# ATMega328P-PU.net
KiCad netlist of a schematic drawn in Altium Designer
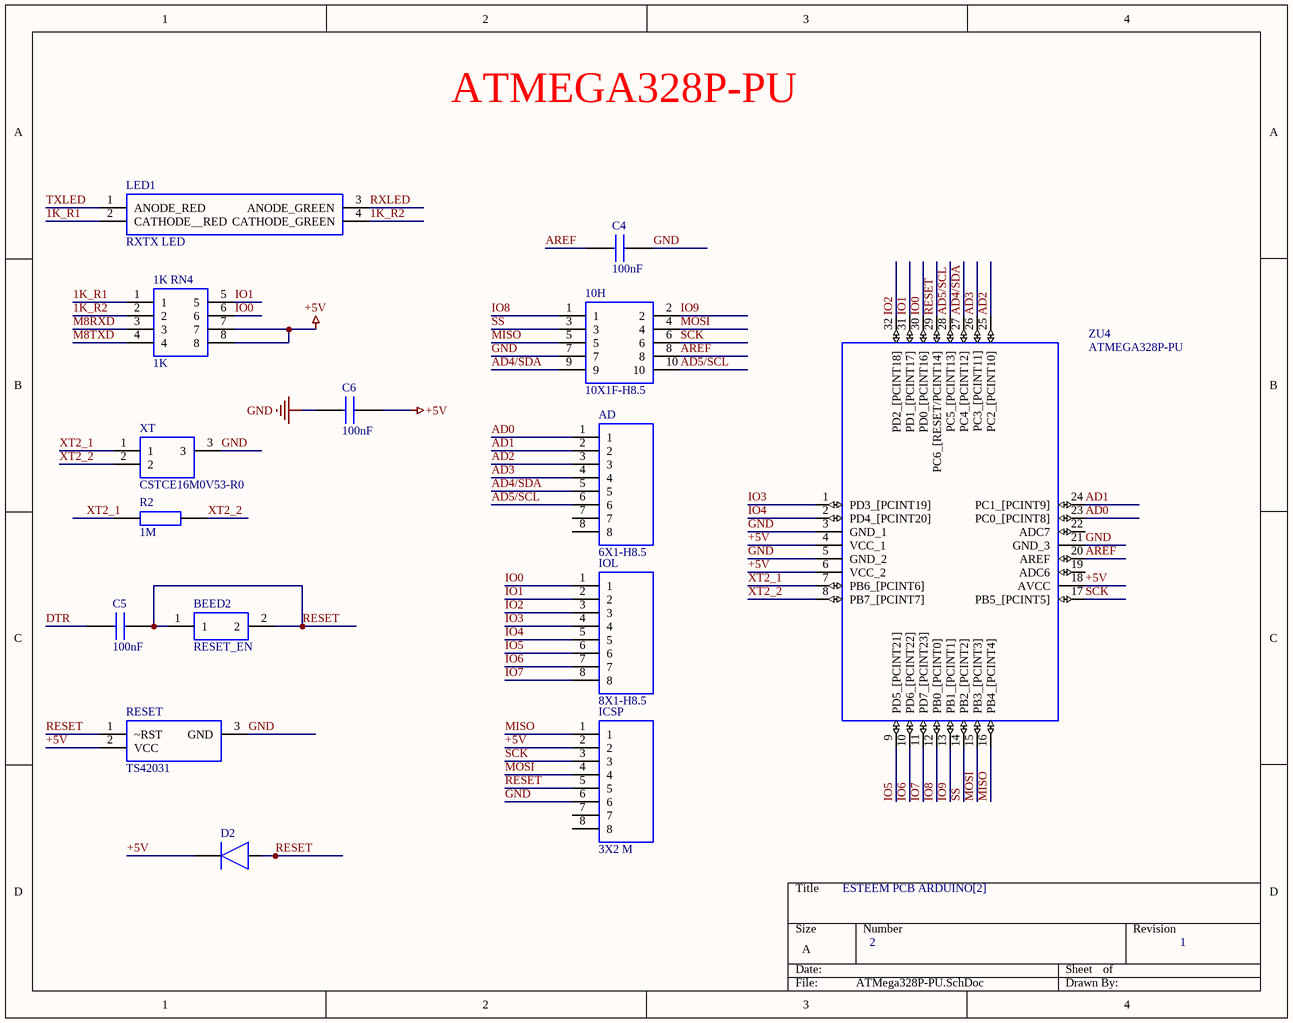
[diagram p0: ATMega328P-PU.SchDoc]

(export (version "E")
  (design (tool "Eeschema 10.0.6"))
  (components
    (comp (ref "1K RN4")
      (value "1K")
      (footprint "CAY10-XXXJ4")
      (fields
        (field (name "MANUFACTURER_PART_NUMBER") "CAY10-220J4LF")
        (field (name "RS PART NUMBER") "1674746")
        (field (name "MOUSER PART NUMBER") "652-CAY10-220J4LF")
      )
      (libsource (lib "22R RN3D") (part "CAY10-220J4LF"))
    )
    (comp (ref "10H")
      (value "10X1F-H8.5")
      (footprint "FTMH10503LDV")
      (fields
        (field (name "MANUFACTURER_PART_NUMBER") "FTMH-105-03-L-DV")
        (field (name "RS PART NUMBER") "7668984P")
        (field (name "MOUSER PART NUMBER") "200-FTMH10503LDV")
      )
      (libsource (lib "10X1F-H8.5") (part "FTMH-105-03-L-DV"))
    )
    (comp (ref "AD")
      (value "6X1-H8.5")
      (footprint "HDRV8W90P0X254_1X8_2032X249X560P")
      (fields
        (field (name "MANUFACTURER_PART_NUMBER") "90120-0768")
        (field (name "RS PART NUMBER") "1671900")
        (field (name "MOUSER PART NUMBER") "538-90120-0768")
      )
      (libsource (lib "8X1F-H8.5") (part "90120-0768"))
    )
    (comp (ref "BEED2")
      (value "RESET_EN")
      (footprint "BEADC2012X105N")
      (description "Chip Ferrite Bead 600R 0805 300mA 1LN")
      (fields
        (field (name "MANUFACTURER_PART_NUMBER") "BLM21BD601SH1D")
        (field (name "RS PART NUMBER") "1048541P")
      )
      (libsource (lib "Ferride Bead") (part "BLM21BD601SH1D"))
    )
    (comp (ref "C4")
      (value "100nF")
      (footprint "CAPC2012X130N")
      (fields
        (field (name "MANUFACTURER_PART_NUMBER") "0805Y0500104KXT")
        (field (name "RS PART NUMBER") "7738389P")
      )
      (libsource (lib "100nF") (part "0805Y0500104KXT"))
    )
    (comp (ref "C5")
      (value "100nF")
      (footprint "CAPC2012X130N")
      (fields
        (field (name "MANUFACTURER_PART_NUMBER") "0805Y0500104KXT")
        (field (name "RS PART NUMBER") "7738389P")
      )
      (libsource (lib "100nF") (part "0805Y0500104KXT"))
    )
    (comp (ref "C6")
      (value "100nF")
      (footprint "CAPC2012X130N")
      (fields
        (field (name "MANUFACTURER_PART_NUMBER") "0805Y0500104KXT")
        (field (name "RS PART NUMBER") "7738389P")
      )
      (libsource (lib "100nF") (part "0805Y0500104KXT"))
    )
    (comp (ref "D2")
      (value "CD1206-S01575")
      (footprint "DIOC3016X65N")
      (fields
        (field (name "RS PART NUMBER") "1775431")
        (field (name "MOUSER PART NUMBER") "652-CD1206-S01575")
      )
      (libsource (lib "CD1206-S01575") (part "CD1206-S01575"))
    )
    (comp (ref "ICSP")
      (value "3X2 M")
      (footprint "HDRV8W90P0X254_1X8_2032X249X560P")
      (fields
        (field (name "MANUFACTURER_PART_NUMBER") "90120-0768")
        (field (name "RS PART NUMBER") "1671900")
        (field (name "MOUSER PART NUMBER") "538-90120-0768")
      )
      (libsource (lib "3x2 Male con") (part "90120-0768"))
    )
    (comp (ref "IOL")
      (value "8X1-H8.5")
      (footprint "HDRV8W90P0X254_1X8_2032X249X560P")
      (fields
        (field (name "MANUFACTURER_PART_NUMBER") "90120-0768")
        (field (name "RS PART NUMBER") "1671900")
        (field (name "MOUSER PART NUMBER") "538-90120-0768")
      )
      (libsource (lib "6X1F-H8.5") (part "90120-0768"))
    )
    (comp (ref "LED1")
      (value "RXTX LED")
      (footprint "SML522MD8WT86")
      (fields
        (field (name "MANUFACTURER_PART_NUMBER") "SML-522MU8WT86")
        (field (name "RS PART NUMBER") "1682468")
        (field (name "MOUSER PART NUMBER") "755-SML-522MU8WT86")
      )
      (libsource (lib "Yellow LED") (part "SML-522MU8WT86"))
    )
    (comp (ref "R2")
      (value "1M")
      (footprint "RESC1608X55N")
      (description "TE CONNECTIVITY - CPF0603B1M0E1 - RES, THIN FILM, 1M, 0.1%, 0.063W, 0603")
      (fields
        (field (name "MANUFACTURER_PART_NUMBER") "CPF0603B1M0E1")
        (field (name "MOUSER PART NUMBER") "279-CPF0603B1M0E1")
      )
      (libsource (lib "1MR") (part "CPF0603B1M0E1"))
    )
    (comp (ref "RESET")
      (value "TS42031")
      (footprint "SOT95P240X110-3N")
      (description "3.3V EconoReset with Pushbutton")
      (fields (field (name "MANUFACTURER_PART_NUMBER") "DS1818R-5+"))
      (libsource (lib "TS42031-160R-TR-7260") (part "DS1818R-5+"))
    )
    (comp (ref "XT")
      (value "CSTCE16M0V53-R0")
      (footprint "CSTCE-V")
      (fields
        (field (name "RS PART NUMBER") "7926524P")
        (field (name "MOUSER PART NUMBER") "81-CSTCE16M0V53-R0")
      )
      (libsource (lib "CSTCE16M0V53-R0") (part "CSTCE16M0V53-R0"))
    )
    (comp (ref "ZU4")
      (value "ATMEGA328P-PU")
      (footprint "QFP80P900X900X120-32N")
      (description "MICROCHIP - ATMEGA328P-AU. - MICROCONTROLLER MCU, 8 BIT, ATMEGA, 20MHZ, TQFP-32")
      (fields
        (field (name "MANUFACTURER_PART_NUMBER") "ATMEGA328P-AU")
        (field (name "RS PART NUMBER") "1310271")
      )
      (libsource (lib "ATMega328P-PU") (part "ATMEGA328P-AU"))
    )
  )
  (nets
    (net (code "1") (name "+5V") (class "Default")
      (node (ref "1K RN4") (pin "7") (pinfunction "7_7") (pintype "passive"))
      (node (ref "1K RN4") (pin "8") (pinfunction "8_8") (pintype "passive"))
      (node (ref "C6") (pin "2") (pinfunction "2_2") (pintype "passive"))
      (node (ref "D2") (pin "1") (pinfunction "K_1") (pintype "passive"))
      (node (ref "ICSP") (pin "2") (pinfunction "2_2") (pintype "passive"))
      (node (ref "RESET") (pin "2") (pinfunction "VCC_2") (pintype "passive"))
      (node (ref "ZU4") (pin "18") (pinfunction "AVCC_18") (pintype "power_in"))
      (node (ref "ZU4") (pin "4") (pinfunction "VCC_1_4") (pintype "power_in"))
      (node (ref "ZU4") (pin "6") (pinfunction "VCC_2_6") (pintype "power_in"))
    )
    (net (code "2") (name "/1K_R1") (class "Default")
      (node (ref "1K RN4") (pin "1") (pinfunction "1_1") (pintype "passive"))
      (node (ref "LED1") (pin "2") (pinfunction "CATHODE__RED_2") (pintype "passive"))
    )
    (net (code "3") (name "/1K_R2") (class "Default")
      (node (ref "1K RN4") (pin "2") (pinfunction "2_2") (pintype "passive"))
      (node (ref "LED1") (pin "4") (pinfunction "CATHODE_GREEN_4") (pintype "passive"))
    )
    (net (code "4") (name "/AD0") (class "Default")
      (node (ref "AD") (pin "1") (pinfunction "1_1") (pintype "passive"))
      (node (ref "ZU4") (pin "23") (pinfunction "PC0_[PCINT8]_23") (pintype "bidirectional"))
    )
    (net (code "5") (name "/AD1") (class "Default")
      (node (ref "AD") (pin "2") (pinfunction "2_2") (pintype "passive"))
      (node (ref "ZU4") (pin "24") (pinfunction "PC1_[PCINT9]_24") (pintype "bidirectional"))
    )
    (net (code "6") (name "/AD2") (class "Default")
      (node (ref "AD") (pin "3") (pinfunction "3_3") (pintype "passive"))
      (node (ref "ZU4") (pin "25") (pinfunction "PC2_[PCINT10]_25") (pintype "bidirectional"))
    )
    (net (code "7") (name "/AD3") (class "Default")
      (node (ref "AD") (pin "4") (pinfunction "4_4") (pintype "passive"))
      (node (ref "ZU4") (pin "26") (pinfunction "PC3_[PCINT11]_26") (pintype "bidirectional"))
    )
    (net (code "8") (name "/AD4{slash}SDA") (class "Default")
      (node (ref "10H") (pin "9") (pinfunction "9_9") (pintype "passive"))
      (node (ref "AD") (pin "5") (pinfunction "5_5") (pintype "passive"))
      (node (ref "ZU4") (pin "27") (pinfunction "PC4_[PCINT12]_27") (pintype "bidirectional"))
    )
    (net (code "9") (name "/AD5{slash}SCL") (class "Default")
      (node (ref "10H") (pin "10") (pinfunction "10_10") (pintype "passive"))
      (node (ref "AD") (pin "6") (pinfunction "6_6") (pintype "passive"))
      (node (ref "ZU4") (pin "28") (pinfunction "PC5_[PCINT13]_28") (pintype "bidirectional"))
    )
    (net (code "10") (name "/AREF") (class "Default")
      (node (ref "10H") (pin "8") (pinfunction "8_8") (pintype "passive"))
      (node (ref "C4") (pin "1") (pinfunction "1_1") (pintype "passive"))
      (node (ref "ZU4") (pin "20") (pinfunction "AREF_20") (pintype "bidirectional"))
    )
    (net (code "11") (name "/DTR") (class "Default")
      (node (ref "C5") (pin "1") (pinfunction "1_1") (pintype "passive"))
    )
    (net (code "12") (name "/IO0") (class "Default")
      (node (ref "1K RN4") (pin "6") (pinfunction "6_6") (pintype "passive"))
      (node (ref "IOL") (pin "1") (pinfunction "1_1") (pintype "passive"))
      (node (ref "ZU4") (pin "30") (pinfunction "PD0_[PCINT16]_30") (pintype "bidirectional"))
    )
    (net (code "13") (name "/IO1") (class "Default")
      (node (ref "1K RN4") (pin "5") (pinfunction "5_5") (pintype "passive"))
      (node (ref "IOL") (pin "2") (pinfunction "2_2") (pintype "passive"))
      (node (ref "ZU4") (pin "31") (pinfunction "PD1_[PCINT17]_31") (pintype "bidirectional"))
    )
    (net (code "14") (name "/IO2") (class "Default")
      (node (ref "IOL") (pin "3") (pinfunction "3_3") (pintype "passive"))
      (node (ref "ZU4") (pin "32") (pinfunction "PD2_[PCINT18]_32") (pintype "bidirectional"))
    )
    (net (code "15") (name "/IO3") (class "Default")
      (node (ref "IOL") (pin "4") (pinfunction "4_4") (pintype "passive"))
      (node (ref "ZU4") (pin "1") (pinfunction "PD3_[PCINT19]_1") (pintype "bidirectional"))
    )
    (net (code "16") (name "/IO4") (class "Default")
      (node (ref "IOL") (pin "5") (pinfunction "5_5") (pintype "passive"))
      (node (ref "ZU4") (pin "2") (pinfunction "PD4_[PCINT20]_2") (pintype "bidirectional"))
    )
    (net (code "17") (name "/IO5") (class "Default")
      (node (ref "IOL") (pin "6") (pinfunction "6_6") (pintype "passive"))
      (node (ref "ZU4") (pin "9") (pinfunction "PD5_[PCINT21]_9") (pintype "bidirectional"))
    )
    (net (code "18") (name "/IO6") (class "Default")
      (node (ref "IOL") (pin "7") (pinfunction "7_7") (pintype "passive"))
      (node (ref "ZU4") (pin "10") (pinfunction "PD6_[PCINT22]_10") (pintype "bidirectional"))
    )
    (net (code "19") (name "/IO7") (class "Default")
      (node (ref "IOL") (pin "8") (pinfunction "8_8") (pintype "passive"))
      (node (ref "ZU4") (pin "11") (pinfunction "PD7_[PCINT23]_11") (pintype "bidirectional"))
    )
    (net (code "20") (name "/IO8") (class "Default")
      (node (ref "10H") (pin "1") (pinfunction "1_1") (pintype "passive"))
      (node (ref "ZU4") (pin "12") (pinfunction "PB0_[PCINT0]_12") (pintype "bidirectional"))
    )
    (net (code "21") (name "/IO9") (class "Default")
      (node (ref "10H") (pin "2") (pinfunction "2_2") (pintype "passive"))
      (node (ref "ZU4") (pin "13") (pinfunction "PB1_[PCINT1]_13") (pintype "bidirectional"))
    )
    (net (code "22") (name "/M8RXD") (class "Default")
      (node (ref "1K RN4") (pin "3") (pinfunction "3_3") (pintype "passive"))
    )
    (net (code "23") (name "/M8TXD") (class "Default")
      (node (ref "1K RN4") (pin "4") (pinfunction "4_4") (pintype "passive"))
    )
    (net (code "24") (name "/MISO") (class "Default")
      (node (ref "10H") (pin "5") (pinfunction "5_5") (pintype "passive"))
      (node (ref "ICSP") (pin "1") (pinfunction "1_1") (pintype "passive"))
      (node (ref "ZU4") (pin "16") (pinfunction "PB4_[PCINT4]_16") (pintype "bidirectional"))
    )
    (net (code "25") (name "/MOSI") (class "Default")
      (node (ref "10H") (pin "4") (pinfunction "4_4") (pintype "passive"))
      (node (ref "ICSP") (pin "4") (pinfunction "4_4") (pintype "passive"))
      (node (ref "ZU4") (pin "15") (pinfunction "PB3_[PCINT3]_15") (pintype "bidirectional"))
    )
    (net (code "26") (name "/RESET") (class "Default")
      (node (ref "BEED2") (pin "1") (pinfunction "1_1") (pintype "passive"))
      (node (ref "BEED2") (pin "2") (pinfunction "2_2") (pintype "passive"))
      (node (ref "C5") (pin "2") (pinfunction "2_2") (pintype "passive"))
      (node (ref "D2") (pin "2") (pinfunction "A_2") (pintype "passive"))
      (node (ref "ICSP") (pin "5") (pinfunction "5_5") (pintype "passive"))
      (node (ref "RESET") (pin "1") (pinfunction "~RST_1") (pintype "passive"))
      (node (ref "ZU4") (pin "29") (pinfunction "PC6_[RESET/PCINT14]_29") (pintype "bidirectional"))
    )
    (net (code "27") (name "/RXLED") (class "Default")
      (node (ref "LED1") (pin "3") (pinfunction "ANODE_GREEN_3") (pintype "passive"))
    )
    (net (code "28") (name "/SCK") (class "Default")
      (node (ref "10H") (pin "6") (pinfunction "6_6") (pintype "passive"))
      (node (ref "ICSP") (pin "3") (pinfunction "3_3") (pintype "passive"))
      (node (ref "ZU4") (pin "17") (pinfunction "PB5_[PCINT5]_17") (pintype "bidirectional"))
    )
    (net (code "29") (name "/SS") (class "Default")
      (node (ref "10H") (pin "3") (pinfunction "3_3") (pintype "passive"))
      (node (ref "ZU4") (pin "14") (pinfunction "PB2_[PCINT2]_14") (pintype "bidirectional"))
    )
    (net (code "30") (name "/TXLED") (class "Default")
      (node (ref "LED1") (pin "1") (pinfunction "ANODE_RED_1") (pintype "passive"))
    )
    (net (code "31") (name "/XT2_1") (class "Default")
      (node (ref "R2") (pin "1") (pinfunction "1_1") (pintype "passive"))
      (node (ref "XT") (pin "1") (pinfunction "1_1") (pintype "passive"))
      (node (ref "ZU4") (pin "7") (pinfunction "PB6_[PCINT6]_7") (pintype "bidirectional"))
    )
    (net (code "32") (name "/XT2_2") (class "Default")
      (node (ref "R2") (pin "2") (pinfunction "2_2") (pintype "passive"))
      (node (ref "XT") (pin "2") (pinfunction "2_2") (pintype "passive"))
      (node (ref "ZU4") (pin "8") (pinfunction "PB7_[PCINT7]_8") (pintype "bidirectional"))
    )
    (net (code "33") (name "GND") (class "Default")
      (node (ref "10H") (pin "7") (pinfunction "7_7") (pintype "passive"))
      (node (ref "C4") (pin "2") (pinfunction "2_2") (pintype "passive"))
      (node (ref "C6") (pin "1") (pinfunction "1_1") (pintype "passive"))
      (node (ref "ICSP") (pin "6") (pinfunction "6_6") (pintype "passive"))
      (node (ref "RESET") (pin "3") (pinfunction "GND_3") (pintype "passive"))
      (node (ref "XT") (pin "3") (pinfunction "3_3") (pintype "passive"))
      (node (ref "ZU4") (pin "21") (pinfunction "GND_3_21") (pintype "passive"))
      (node (ref "ZU4") (pin "3") (pinfunction "GND_1_3") (pintype "passive"))
      (node (ref "ZU4") (pin "5") (pinfunction "GND_2_5") (pintype "passive"))
    )
    (net (code "34") (name "unconnected-(AD-Pad7)") (class "Default")
      (node (ref "AD") (pin "7") (pinfunction "7_7") (pintype "passive"))
    )
    (net (code "35") (name "unconnected-(AD-Pad8)") (class "Default")
      (node (ref "AD") (pin "8") (pinfunction "8_8") (pintype "passive"))
    )
    (net (code "36") (name "unconnected-(ICSP-Pad7)") (class "Default")
      (node (ref "ICSP") (pin "7") (pinfunction "7_7") (pintype "passive"))
    )
    (net (code "37") (name "unconnected-(ICSP-Pad8)") (class "Default")
      (node (ref "ICSP") (pin "8") (pinfunction "8_8") (pintype "passive"))
    )
    (net (code "38") (name "unconnected-(ZU4-ADC6-Pad19)") (class "Default")
      (node (ref "ZU4") (pin "19") (pinfunction "ADC6_19") (pintype "bidirectional"))
    )
    (net (code "39") (name "unconnected-(ZU4-ADC7-Pad22)") (class "Default")
      (node (ref "ZU4") (pin "22") (pinfunction "ADC7_22") (pintype "bidirectional"))
    )
  )
)
